# MPU_6050_Adapter.net
KiCad netlist of a schematic drawn in EasyEDA Pro
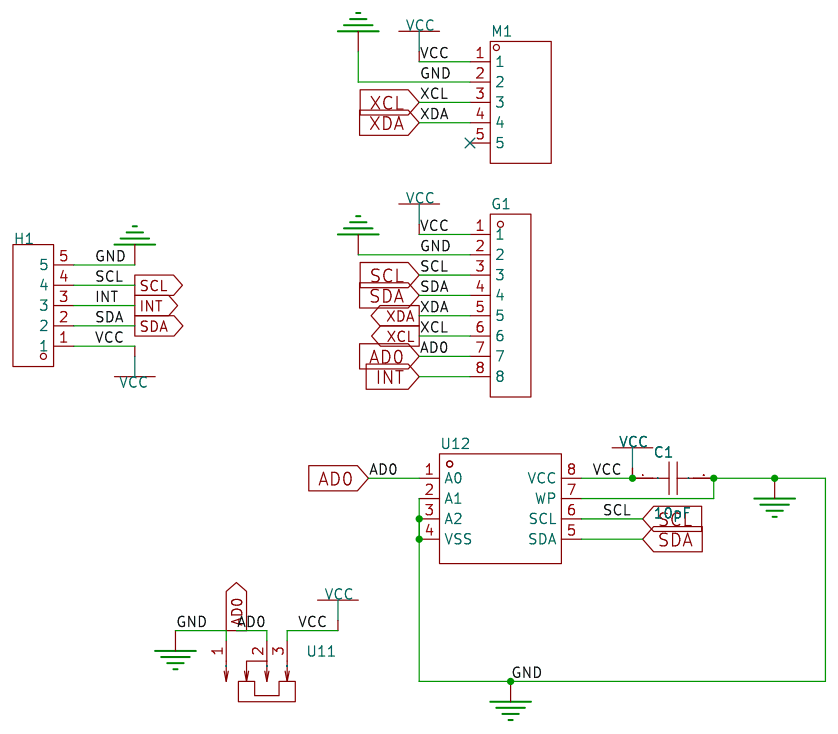
[diagram p0: schematic sheet]

(export (version "E")
  (design (tool "Eeschema 10.0.6"))
  (components
    (comp (ref "C1")
      (value "10pF")
      (footprint "easyedapro:C0402")
      (fields
        (field (name "Manufacturer Part") "CL05C100JB5NNNC")
        (field (name "Manufacturer") "SAMSUNG(三星)")
      )
      (libsource (lib "easyedapro") (part "CL05C100JB5NNNC"))
    )
    (comp (ref "G1")
      (value "~")
      (footprint "easyedapro:MPU6050")
      (libsource (lib "easyedapro") (part "PZ200-1-08-Z"))
    )
    (comp (ref "H1")
      (value "~")
      (footprint "easyedapro:HDR-TH_5P-P2.54-V-M")
      (fields (field (name "Manufacturer Part") "PZ254V-11-05P") (field (name "Manufacturer") "XFCN(兴飞)"))
      (libsource (lib "easyedapro") (part "PZ254V-11-05P"))
    )
    (comp (ref "M1")
      (value "~")
      (footprint "easyedapro:GY-271")
      (libsource (lib "easyedapro") (part "77311-462K05LF"))
    )
    (comp (ref "U11")
      (value "~")
      (footprint "easyedapro:SW-TH_SK-3260D-01-LX")
      (fields
        (field (name "Manufacturer Part") "SK-3260D-01-L1")
        (field (name "Manufacturer") "XKB Connectivity(中国星坤)")
      )
      (libsource (lib "easyedapro") (part "SK-3260D-01-L1"))
    )
    (comp (ref "U12")
      (value "~")
      (footprint "easyedapro:SOIC-8_L4.9-W3.9-P1.27-LS6.0-BL")
      (description "存储器容量:256Kb (32K x 8);存储器接口类型:I2C;工作电压:1.8V ~ 5.5V;")
      (fields
        (field (name "Manufacturer Part") "CAT24C256WI-GT3")
        (field (name "Manufacturer") "onsemi(安森美)")
      )
      (libsource (lib "easyedapro") (part "CAT24C256WI-GT3"))
    )
  )
  (nets
    (net (code "1") (name "AD0") (class "Default")
      (node (ref "G1") (pin "7") (pinfunction "7_7") (pintype "input"))
      (node (ref "U11") (pin "2") (pinfunction "2_2") (pintype "input"))
      (node (ref "U12") (pin "1") (pinfunction "A0_1") (pintype "input"))
    )
    (net (code "2") (name "GND") (class "Default")
      (node (ref "C1") (pin "2") (pinfunction "2_2") (pintype "input"))
      (node (ref "G1") (pin "2") (pinfunction "2_2") (pintype "input"))
      (node (ref "H1") (pin "5") (pinfunction "5_5") (pintype "input"))
      (node (ref "M1") (pin "2") (pinfunction "2_2") (pintype "input"))
      (node (ref "U11") (pin "1") (pinfunction "1_1") (pintype "input"))
      (node (ref "U12") (pin "2") (pinfunction "A1_2") (pintype "input"))
      (node (ref "U12") (pin "3") (pinfunction "A2_3") (pintype "input"))
      (node (ref "U12") (pin "4") (pinfunction "VSS_4") (pintype "input"))
      (node (ref "U12") (pin "7") (pinfunction "WP_7") (pintype "input"))
    )
    (net (code "3") (name "INT") (class "Default")
      (node (ref "G1") (pin "8") (pinfunction "8_8") (pintype "input"))
      (node (ref "H1") (pin "3") (pinfunction "3_3") (pintype "input"))
    )
    (net (code "4") (name "SCL") (class "Default")
      (node (ref "G1") (pin "3") (pinfunction "3_3") (pintype "input"))
      (node (ref "H1") (pin "4") (pinfunction "4_4") (pintype "input"))
      (node (ref "U12") (pin "6") (pinfunction "SCL_6") (pintype "input"))
    )
    (net (code "5") (name "SDA") (class "Default")
      (node (ref "G1") (pin "4") (pinfunction "4_4") (pintype "input"))
      (node (ref "H1") (pin "2") (pinfunction "2_2") (pintype "input"))
      (node (ref "U12") (pin "5") (pinfunction "SDA_5") (pintype "input"))
    )
    (net (code "6") (name "VCC") (class "Default")
      (node (ref "C1") (pin "1") (pinfunction "1_1") (pintype "input"))
      (node (ref "G1") (pin "1") (pinfunction "1_1") (pintype "input"))
      (node (ref "H1") (pin "1") (pinfunction "1_1") (pintype "input"))
      (node (ref "M1") (pin "1") (pinfunction "1_1") (pintype "input"))
      (node (ref "U11") (pin "3") (pinfunction "3_3") (pintype "input"))
      (node (ref "U12") (pin "8") (pinfunction "VCC_8") (pintype "input"))
    )
    (net (code "7") (name "XCL") (class "Default")
      (node (ref "G1") (pin "6") (pinfunction "6_6") (pintype "input"))
      (node (ref "M1") (pin "3") (pinfunction "3_3") (pintype "input"))
    )
    (net (code "8") (name "XDA") (class "Default")
      (node (ref "G1") (pin "5") (pinfunction "5_5") (pintype "input"))
      (node (ref "M1") (pin "4") (pinfunction "4_4") (pintype "input"))
    )
    (net (code "9") (name "unconnected-(M1-Pad5)") (class "Default")
      (node (ref "M1") (pin "5") (pinfunction "5_5") (pintype "input+no_connect"))
    )
  )
)
